# NodeBodyControl.net
KiCad netlist of a schematic drawn in Altium Designer
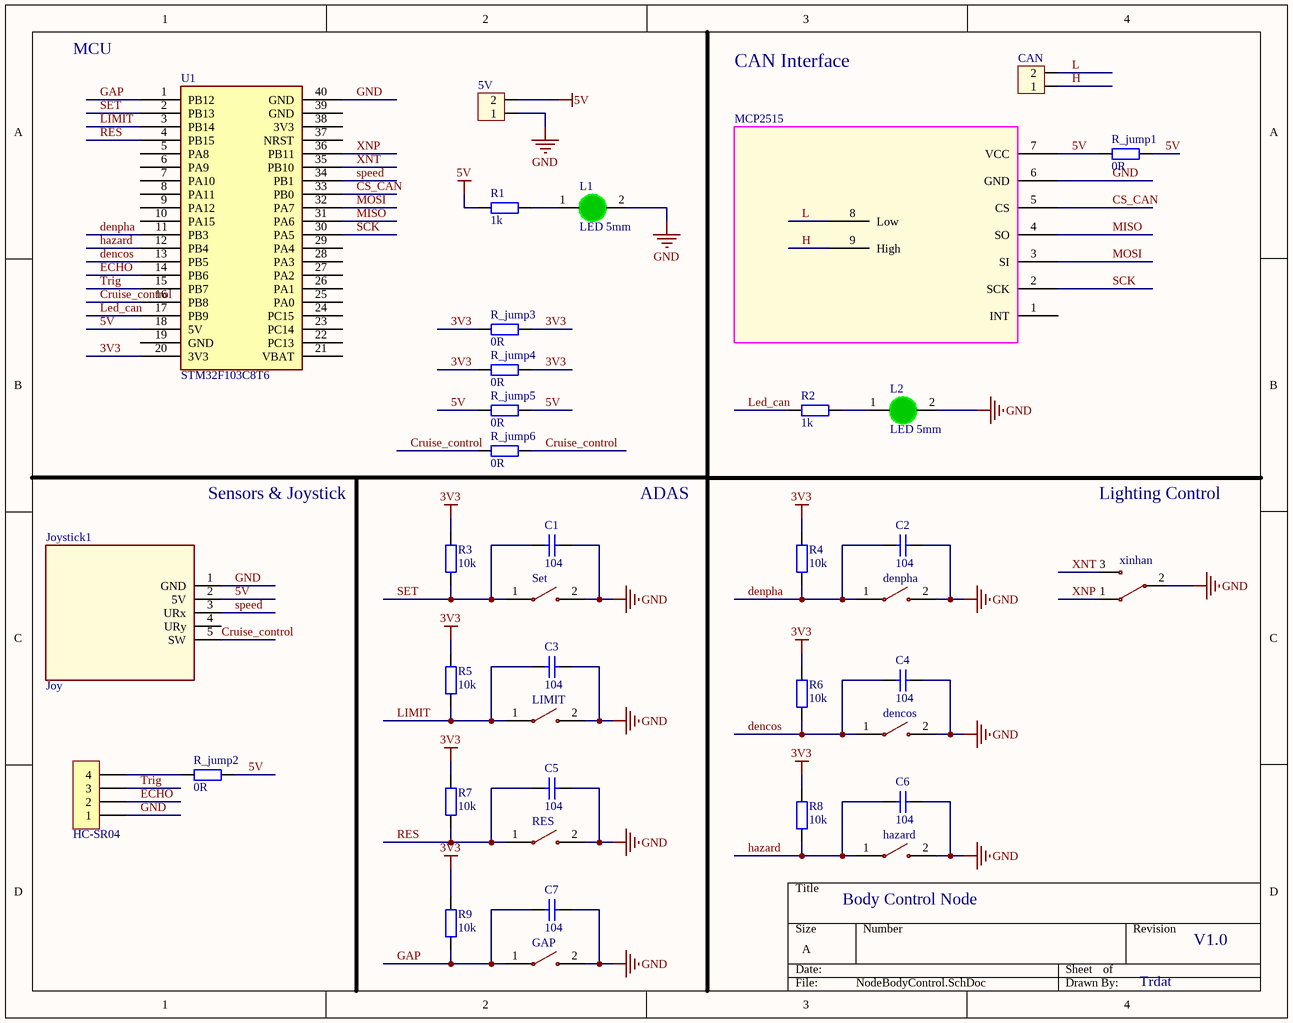
[diagram p0: NodeBodyControl.SchDoc]

(export (version "E")
  (design (tool "Eeschema 10.0.6"))
  (components
    (comp (ref "5V")
      (value "Header 2P 2.54 Duc Cong")
      (footprint "Header 2P DC 2.54")
      (description "Cắm")
      (libsource (lib "Altium_Lib_by_KhueNguyenCreator") (part "Header 2P 2.54 Duc Cong"))
    )
    (comp (ref "C1")
      (value "104")
      (footprint "tu gom")
      (description "Cắm")
      (libsource (lib "Altium_Lib_by_KhueNguyenCreator") (part "Tu gom 104 50V"))
    )
    (comp (ref "C2")
      (value "104")
      (footprint "tu gom")
      (description "Cắm")
      (libsource (lib "Altium_Lib_by_KhueNguyenCreator") (part "Tu gom 104 50V"))
    )
    (comp (ref "C3")
      (value "104")
      (footprint "tu gom")
      (description "Cắm")
      (libsource (lib "Altium_Lib_by_KhueNguyenCreator") (part "Tu gom 104 50V"))
    )
    (comp (ref "C4")
      (value "104")
      (footprint "tu gom")
      (description "Cắm")
      (libsource (lib "Altium_Lib_by_KhueNguyenCreator") (part "Tu gom 104 50V"))
    )
    (comp (ref "C5")
      (value "104")
      (footprint "tu gom")
      (description "Cắm")
      (libsource (lib "Altium_Lib_by_KhueNguyenCreator") (part "Tu gom 104 50V"))
    )
    (comp (ref "C6")
      (value "104")
      (footprint "tu gom")
      (description "Cắm")
      (libsource (lib "Altium_Lib_by_KhueNguyenCreator") (part "Tu gom 104 50V"))
    )
    (comp (ref "C7")
      (value "104")
      (footprint "tu gom")
      (description "Cắm")
      (libsource (lib "Altium_Lib_by_KhueNguyenCreator") (part "Tu gom 104 50V"))
    )
    (comp (ref "CAN")
      (value "~")
      (footprint "Header 2P DC 2.54")
      (description "Cắm")
      (libsource (lib "Altium_Lib_by_KhueNguyenCreator") (part "Header 2P 2.54 Duc Cong"))
    )
    (comp (ref "dencos")
      (value "PUSH_BUTTON_12X12")
      (footprint "PUSH_BUTTON_12X12_YELLOW")
      (description "Push Button Tactile Switch PTH 4 Pins 12x12mm.")
      (libsource (lib "Buttons & Switches") (part "PUSH_BUTTON_12X12"))
    )
    (comp (ref "denpha")
      (value "PUSH_BUTTON_12X12")
      (footprint "PUSH_BUTTON_12X12_YELLOW")
      (description "Push Button Tactile Switch PTH 4 Pins 12x12mm.")
      (libsource (lib "Buttons & Switches") (part "PUSH_BUTTON_12X12"))
    )
    (comp (ref "GAP")
      (value "PUSH_BUTTON_12X12")
      (footprint "PUSH_BUTTON_12X12_YELLOW")
      (description "Push Button Tactile Switch PTH 4 Pins 12x12mm.")
      (libsource (lib "Buttons & Switches") (part "PUSH_BUTTON_12X12"))
    )
    (comp (ref "H1")
      (value "HC-SR04")
      (footprint "Header 4P DC 2.54")
      (description "Cắm")
      (libsource (lib "My_Component_Library") (part "Header 4P 2.54 Duc Cong"))
    )
    (comp (ref "hazard")
      (value "PUSH_BUTTON_12X12")
      (footprint "PUSH_BUTTON_12X12_RED")
      (description "Push Button Tactile Switch PTH 4 Pins 12x12mm.")
      (libsource (lib "Buttons & Switches") (part "PUSH_BUTTON_12X12"))
    )
    (comp (ref "Joystick1")
      (value "Joy")
      (footprint "Joystick")
      (libsource (lib "My_Component_Library") (part "Joy"))
    )
    (comp (ref "L1")
      (value "LED 5mm")
      (footprint "LED-5MM-Green")
      (description "Cắm")
      (libsource (lib "Altium_Lib_by_KhueNguyenCreator") (part "LED 5mm Xanh La"))
    )
    (comp (ref "L2")
      (value "LED 5mm")
      (footprint "LED-5MM-Green")
      (description "Cắm")
      (libsource (lib "Altium_Lib_by_KhueNguyenCreator") (part "LED 5mm Xanh La"))
    )
    (comp (ref "LIMIT")
      (value "PUSH_BUTTON_12X12")
      (footprint "PUSH_BUTTON_12X12_YELLOW")
      (description "Push Button Tactile Switch PTH 4 Pins 12x12mm.")
      (libsource (lib "Buttons & Switches") (part "PUSH_BUTTON_12X12"))
    )
    (comp (ref "MCP2515")
      (value "MCP2515")
      (footprint "MCP2515_MODULE")
      (libsource (lib "My_Component_Library") (part "MCP2515"))
    )
    (comp (ref "R1")
      (value "1k")
      (footprint "tro vach 1/4w")
      (description "Cắm")
      (libsource (lib "Altium_Lib_by_KhueNguyenCreator") (part "Tro Vach 1/4W 5% 1k"))
    )
    (comp (ref "R2")
      (value "1k")
      (footprint "tro vach 1/4w")
      (description "Cắm")
      (libsource (lib "Altium_Lib_by_KhueNguyenCreator") (part "Tro Vach 1/4W 5% 1k"))
    )
    (comp (ref "R3")
      (value "10k")
      (footprint "tro vach 1/4w")
      (description "Căm")
      (libsource (lib "Altium_Lib_by_KhueNguyenCreator") (part "Tro Vach 1/4W 5% 10k"))
    )
    (comp (ref "R4")
      (value "10k")
      (footprint "tro vach 1/4w")
      (description "Căm")
      (libsource (lib "Altium_Lib_by_KhueNguyenCreator") (part "Tro Vach 1/4W 5% 10k"))
    )
    (comp (ref "R5")
      (value "10k")
      (footprint "tro vach 1/4w")
      (description "Căm")
      (libsource (lib "Altium_Lib_by_KhueNguyenCreator") (part "Tro Vach 1/4W 5% 10k"))
    )
    (comp (ref "R6")
      (value "10k")
      (footprint "tro vach 1/4w")
      (description "Căm")
      (libsource (lib "Altium_Lib_by_KhueNguyenCreator") (part "Tro Vach 1/4W 5% 10k"))
    )
    (comp (ref "R7")
      (value "10k")
      (footprint "tro vach 1/4w")
      (description "Căm")
      (libsource (lib "Altium_Lib_by_KhueNguyenCreator") (part "Tro Vach 1/4W 5% 10k"))
    )
    (comp (ref "R8")
      (value "10k")
      (footprint "tro vach 1/4w")
      (description "Căm")
      (libsource (lib "Altium_Lib_by_KhueNguyenCreator") (part "Tro Vach 1/4W 5% 10k"))
    )
    (comp (ref "R9")
      (value "10k")
      (footprint "tro vach 1/4w")
      (description "Căm")
      (libsource (lib "Altium_Lib_by_KhueNguyenCreator") (part "Tro Vach 1/4W 5% 10k"))
    )
    (comp (ref "RES")
      (value "PUSH_BUTTON_12X12")
      (footprint "PUSH_BUTTON_12X12_YELLOW")
      (description "Push Button Tactile Switch PTH 4 Pins 12x12mm.")
      (libsource (lib "Buttons & Switches") (part "PUSH_BUTTON_12X12"))
    )
    (comp (ref "R_jump1")
      (value "0R")
      (footprint "tro vach 1/4w")
      (description "Cắm")
      (libsource (lib "Altium_Lib_by_KhueNguyenCreator") (part "Tro Vach 1/4W 5% 0.11R"))
    )
    (comp (ref "R_jump2")
      (value "0R")
      (footprint "tro vach 1/4w")
      (description "Cắm")
      (libsource (lib "Altium_Lib_by_KhueNguyenCreator") (part "Tro Vach 1/4W 5% 0.11R"))
    )
    (comp (ref "R_jump3")
      (value "0R")
      (footprint "tro vach 1/4w")
      (description "Cắm")
      (libsource (lib "Altium_Lib_by_KhueNguyenCreator") (part "Tro Vach 1/4W 5% 0.11R"))
    )
    (comp (ref "R_jump4")
      (value "0R")
      (footprint "tro vach 1/4w")
      (description "Cắm")
      (libsource (lib "Altium_Lib_by_KhueNguyenCreator") (part "Tro Vach 1/4W 5% 0.11R"))
    )
    (comp (ref "R_jump5")
      (value "0R")
      (footprint "tro vach 1/4w")
      (description "Cắm")
      (libsource (lib "Altium_Lib_by_KhueNguyenCreator") (part "Tro Vach 1/4W 5% 0.11R"))
    )
    (comp (ref "R_jump6")
      (value "0R")
      (footprint "tro vach 1/4w")
      (description "Cắm")
      (libsource (lib "Altium_Lib_by_KhueNguyenCreator") (part "Tro Vach 1/4W 5% 0.11R"))
    )
    (comp (ref "Set")
      (value "PUSH_BUTTON_12X12")
      (footprint "PUSH_BUTTON_12X12_YELLOW")
      (description "Push Button Tactile Switch PTH 4 Pins 12x12mm.")
      (libsource (lib "Buttons & Switches") (part "PUSH_BUTTON_12X12"))
    )
    (comp (ref "U1")
      (value "STM32F103C8T6")
      (footprint "Stm32 BluePill")
      (description "Designed By @Alixahedi")
      (libsource (lib "Stm32 Blue Pill") (part "BluePill"))
    )
    (comp (ref "xinhan")
      (value "~")
      (footprint "TOGGLE_SWITCH_SPDT")
      (description "Toggle Switch SPDT, 125V AC, 6A, 33x13x7mm.")
      (libsource (lib "Buttons & Switches") (part "TOGGLE_SWITCH_SPDT"))
    )
  )
  (nets
    (net (code "1") (name "/CS_CAN") (class "Default")
      (node (ref "MCP2515") (pin "5") (pinfunction "CS_5") (pintype "passive"))
      (node (ref "U1") (pin "33") (pinfunction "PB0_33") (pintype "passive"))
    )
    (net (code "2") (name "/Cruise_control") (class "Default")
      (node (ref "Joystick1") (pin "5") (pinfunction "SW_5") (pintype "passive"))
      (node (ref "R_jump6") (pin "1") (pinfunction "1_1") (pintype "passive"))
      (node (ref "R_jump6") (pin "2") (pinfunction "2_2") (pintype "passive"))
      (node (ref "U1") (pin "16") (pinfunction "PB8_16") (pintype "passive"))
    )
    (net (code "3") (name "/ECHO") (class "Default")
      (node (ref "H1") (pin "2") (pinfunction "2_2") (pintype "passive"))
      (node (ref "U1") (pin "14") (pinfunction "PB6_14") (pintype "passive"))
    )
    (net (code "4") (name "/GAP") (class "Default")
      (node (ref "C7") (pin "2") (pinfunction "2_2") (pintype "passive"))
      (node (ref "GAP") (pin "1") (pinfunction "1_1") (pintype "passive"))
      (node (ref "R9") (pin "1") (pinfunction "1_1") (pintype "passive"))
      (node (ref "U1") (pin "1") (pinfunction "PB12_1") (pintype "passive"))
    )
    (net (code "5") (name "/H") (class "Default")
      (node (ref "CAN") (pin "1") (pinfunction "1_1") (pintype "passive"))
      (node (ref "MCP2515") (pin "9") (pinfunction "High_9") (pintype "passive"))
    )
    (net (code "6") (name "/L") (class "Default")
      (node (ref "CAN") (pin "2") (pinfunction "2_2") (pintype "passive"))
      (node (ref "MCP2515") (pin "8") (pinfunction "Low_8") (pintype "passive"))
    )
    (net (code "7") (name "/LIMIT") (class "Default")
      (node (ref "C3") (pin "2") (pinfunction "2_2") (pintype "passive"))
      (node (ref "LIMIT") (pin "1") (pinfunction "1_1") (pintype "passive"))
      (node (ref "R5") (pin "1") (pinfunction "1_1") (pintype "passive"))
      (node (ref "U1") (pin "3") (pinfunction "PB14_3") (pintype "passive"))
    )
    (net (code "8") (name "/Led_can") (class "Default")
      (node (ref "R2") (pin "1") (pinfunction "1_1") (pintype "passive"))
      (node (ref "U1") (pin "17") (pinfunction "PB9_17") (pintype "passive"))
    )
    (net (code "9") (name "/MISO") (class "Default")
      (node (ref "MCP2515") (pin "4") (pinfunction "SO_4") (pintype "passive"))
      (node (ref "U1") (pin "31") (pinfunction "PA6_31") (pintype "passive"))
    )
    (net (code "10") (name "/MOSI") (class "Default")
      (node (ref "MCP2515") (pin "3") (pinfunction "SI_3") (pintype "passive"))
      (node (ref "U1") (pin "32") (pinfunction "PA7_32") (pintype "passive"))
    )
    (net (code "11") (name "/RES") (class "Default")
      (node (ref "C5") (pin "2") (pinfunction "2_2") (pintype "passive"))
      (node (ref "R7") (pin "1") (pinfunction "1_1") (pintype "passive"))
      (node (ref "RES") (pin "1") (pinfunction "1_1") (pintype "passive"))
      (node (ref "U1") (pin "4") (pinfunction "PB15_4") (pintype "passive"))
    )
    (net (code "12") (name "/SCK") (class "Default")
      (node (ref "MCP2515") (pin "2") (pinfunction "SCK_2") (pintype "passive"))
      (node (ref "U1") (pin "30") (pinfunction "PA5_30") (pintype "passive"))
    )
    (net (code "13") (name "/SET") (class "Default")
      (node (ref "C1") (pin "2") (pinfunction "2_2") (pintype "passive"))
      (node (ref "R3") (pin "1") (pinfunction "1_1") (pintype "passive"))
      (node (ref "Set") (pin "1") (pinfunction "1_1") (pintype "passive"))
      (node (ref "U1") (pin "2") (pinfunction "PB13_2") (pintype "passive"))
    )
    (net (code "14") (name "/Trig") (class "Default")
      (node (ref "H1") (pin "3") (pinfunction "3_3") (pintype "passive"))
      (node (ref "U1") (pin "15") (pinfunction "PB7_15") (pintype "passive"))
    )
    (net (code "15") (name "/XNP") (class "Default")
      (node (ref "U1") (pin "36") (pinfunction "PB11_36") (pintype "passive"))
      (node (ref "xinhan") (pin "1") (pinfunction "1_1") (pintype "passive"))
    )
    (net (code "16") (name "/XNT") (class "Default")
      (node (ref "U1") (pin "35") (pinfunction "PB10_35") (pintype "passive"))
      (node (ref "xinhan") (pin "3") (pinfunction "3_3") (pintype "passive"))
    )
    (net (code "17") (name "/dencos") (class "Default")
      (node (ref "C4") (pin "2") (pinfunction "2_2") (pintype "passive"))
      (node (ref "R6") (pin "1") (pinfunction "1_1") (pintype "passive"))
      (node (ref "U1") (pin "13") (pinfunction "PB5_13") (pintype "passive"))
      (node (ref "dencos") (pin "1") (pinfunction "1_1") (pintype "passive"))
    )
    (net (code "18") (name "/denpha") (class "Default")
      (node (ref "C2") (pin "2") (pinfunction "2_2") (pintype "passive"))
      (node (ref "R4") (pin "1") (pinfunction "1_1") (pintype "passive"))
      (node (ref "U1") (pin "11") (pinfunction "PB3_11") (pintype "passive"))
      (node (ref "denpha") (pin "1") (pinfunction "1_1") (pintype "passive"))
    )
    (net (code "19") (name "/hazard") (class "Default")
      (node (ref "C6") (pin "2") (pinfunction "2_2") (pintype "passive"))
      (node (ref "R8") (pin "1") (pinfunction "1_1") (pintype "passive"))
      (node (ref "U1") (pin "12") (pinfunction "PB4_12") (pintype "passive"))
      (node (ref "hazard") (pin "1") (pinfunction "1_1") (pintype "passive"))
    )
    (net (code "20") (name "/speed") (class "Default")
      (node (ref "Joystick1") (pin "3") (pinfunction "URx_3") (pintype "passive"))
      (node (ref "U1") (pin "34") (pinfunction "PB1_34") (pintype "passive"))
    )
    (net (code "21") (name "3V3") (class "Default")
      (node (ref "R3") (pin "2") (pinfunction "2_2") (pintype "passive"))
      (node (ref "R4") (pin "2") (pinfunction "2_2") (pintype "passive"))
      (node (ref "R5") (pin "2") (pinfunction "2_2") (pintype "passive"))
      (node (ref "R6") (pin "2") (pinfunction "2_2") (pintype "passive"))
      (node (ref "R7") (pin "2") (pinfunction "2_2") (pintype "passive"))
      (node (ref "R8") (pin "2") (pinfunction "2_2") (pintype "passive"))
      (node (ref "R9") (pin "2") (pinfunction "2_2") (pintype "passive"))
      (node (ref "R_jump3") (pin "1") (pinfunction "1_1") (pintype "passive"))
      (node (ref "R_jump3") (pin "2") (pinfunction "2_2") (pintype "passive"))
      (node (ref "R_jump4") (pin "1") (pinfunction "1_1") (pintype "passive"))
      (node (ref "R_jump4") (pin "2") (pinfunction "2_2") (pintype "passive"))
      (node (ref "U1") (pin "20") (pinfunction "3V3_20") (pintype "passive"))
    )
    (net (code "22") (name "5V") (class "Default")
      (node (ref "5V") (pin "2") (pinfunction "2_2") (pintype "passive"))
      (node (ref "Joystick1") (pin "2") (pinfunction "5V_2") (pintype "power_in"))
      (node (ref "MCP2515") (pin "7") (pinfunction "VCC_7") (pintype "power_in"))
      (node (ref "R1") (pin "1") (pinfunction "1_1") (pintype "passive"))
      (node (ref "R_jump1") (pin "1") (pinfunction "1_1") (pintype "passive"))
      (node (ref "R_jump1") (pin "2") (pinfunction "2_2") (pintype "passive"))
      (node (ref "R_jump2") (pin "2") (pinfunction "2_2") (pintype "passive"))
      (node (ref "R_jump5") (pin "1") (pinfunction "1_1") (pintype "passive"))
      (node (ref "R_jump5") (pin "2") (pinfunction "2_2") (pintype "passive"))
      (node (ref "U1") (pin "18") (pinfunction "5V_18") (pintype "passive"))
    )
    (net (code "23") (name "GND") (class "Default")
      (node (ref "5V") (pin "1") (pinfunction "1_1") (pintype "passive"))
      (node (ref "C1") (pin "1") (pinfunction "1_1") (pintype "passive"))
      (node (ref "C2") (pin "1") (pinfunction "1_1") (pintype "passive"))
      (node (ref "C3") (pin "1") (pinfunction "1_1") (pintype "passive"))
      (node (ref "C4") (pin "1") (pinfunction "1_1") (pintype "passive"))
      (node (ref "C5") (pin "1") (pinfunction "1_1") (pintype "passive"))
      (node (ref "C6") (pin "1") (pinfunction "1_1") (pintype "passive"))
      (node (ref "C7") (pin "1") (pinfunction "1_1") (pintype "passive"))
      (node (ref "GAP") (pin "2") (pinfunction "2_2") (pintype "passive"))
      (node (ref "H1") (pin "1") (pinfunction "1_1") (pintype "passive"))
      (node (ref "Joystick1") (pin "1") (pinfunction "GND_1") (pintype "power_in"))
      (node (ref "L1") (pin "2") (pinfunction "K_2") (pintype "passive"))
      (node (ref "L2") (pin "2") (pinfunction "K_2") (pintype "passive"))
      (node (ref "LIMIT") (pin "2") (pinfunction "2_2") (pintype "passive"))
      (node (ref "MCP2515") (pin "6") (pinfunction "GND_6") (pintype "power_in"))
      (node (ref "RES") (pin "2") (pinfunction "2_2") (pintype "passive"))
      (node (ref "Set") (pin "2") (pinfunction "2_2") (pintype "passive"))
      (node (ref "U1") (pin "40") (pinfunction "GND_40") (pintype "passive"))
      (node (ref "dencos") (pin "2") (pinfunction "2_2") (pintype "passive"))
      (node (ref "denpha") (pin "2") (pinfunction "2_2") (pintype "passive"))
      (node (ref "hazard") (pin "2") (pinfunction "2_2") (pintype "passive"))
      (node (ref "xinhan") (pin "2") (pinfunction "2_2") (pintype "passive"))
    )
    (net (code "24") (name "Net-(H1-Pad4)") (class "Default")
      (node (ref "H1") (pin "4") (pinfunction "4_4") (pintype "passive"))
      (node (ref "R_jump2") (pin "1") (pinfunction "1_1") (pintype "passive"))
    )
    (net (code "25") (name "Net-(L1-A)") (class "Default")
      (node (ref "L1") (pin "1") (pinfunction "A_1") (pintype "passive"))
      (node (ref "R1") (pin "2") (pinfunction "2_2") (pintype "passive"))
    )
    (net (code "26") (name "Net-(L2-A)") (class "Default")
      (node (ref "L2") (pin "1") (pinfunction "A_1") (pintype "passive"))
      (node (ref "R2") (pin "2") (pinfunction "2_2") (pintype "passive"))
    )
    (net (code "27") (name "unconnected-(Joystick1-URy-Pad4)") (class "Default")
      (node (ref "Joystick1") (pin "4") (pinfunction "URy_4") (pintype "passive"))
    )
    (net (code "28") (name "unconnected-(MCP2515-INT-Pad1)") (class "Default")
      (node (ref "MCP2515") (pin "1") (pinfunction "INT_1") (pintype "passive"))
    )
    (net (code "29") (name "unconnected-(U1-3V3-Pad38)") (class "Default")
      (node (ref "U1") (pin "38") (pinfunction "3V3_38") (pintype "passive"))
    )
    (net (code "30") (name "unconnected-(U1-GND-Pad19)") (class "Default")
      (node (ref "U1") (pin "19") (pinfunction "GND_19") (pintype "passive"))
    )
    (net (code "31") (name "unconnected-(U1-GND-Pad39)") (class "Default")
      (node (ref "U1") (pin "39") (pinfunction "GND_39") (pintype "passive"))
    )
    (net (code "32") (name "unconnected-(U1-NRST-Pad37)") (class "Default")
      (node (ref "U1") (pin "37") (pinfunction "NRST_37") (pintype "passive"))
    )
    (net (code "33") (name "unconnected-(U1-PA0-Pad25)") (class "Default")
      (node (ref "U1") (pin "25") (pinfunction "PA0_25") (pintype "passive"))
    )
    (net (code "34") (name "unconnected-(U1-PA1-Pad26)") (class "Default")
      (node (ref "U1") (pin "26") (pinfunction "PA1_26") (pintype "passive"))
    )
    (net (code "35") (name "unconnected-(U1-PA2-Pad27)") (class "Default")
      (node (ref "U1") (pin "27") (pinfunction "PA2_27") (pintype "passive"))
    )
    (net (code "36") (name "unconnected-(U1-PA3-Pad28)") (class "Default")
      (node (ref "U1") (pin "28") (pinfunction "PA3_28") (pintype "passive"))
    )
    (net (code "37") (name "unconnected-(U1-PA4-Pad29)") (class "Default")
      (node (ref "U1") (pin "29") (pinfunction "PA4_29") (pintype "passive"))
    )
    (net (code "38") (name "unconnected-(U1-PA8-Pad5)") (class "Default")
      (node (ref "U1") (pin "5") (pinfunction "PA8_5") (pintype "passive"))
    )
    (net (code "39") (name "unconnected-(U1-PA9-Pad6)") (class "Default")
      (node (ref "U1") (pin "6") (pinfunction "PA9_6") (pintype "passive"))
    )
    (net (code "40") (name "unconnected-(U1-PA10-Pad7)") (class "Default")
      (node (ref "U1") (pin "7") (pinfunction "PA10_7") (pintype "passive"))
    )
    (net (code "41") (name "unconnected-(U1-PA11-Pad8)") (class "Default")
      (node (ref "U1") (pin "8") (pinfunction "PA11_8") (pintype "passive"))
    )
    (net (code "42") (name "unconnected-(U1-PA12-Pad9)") (class "Default")
      (node (ref "U1") (pin "9") (pinfunction "PA12_9") (pintype "passive"))
    )
    (net (code "43") (name "unconnected-(U1-PA15-Pad10)") (class "Default")
      (node (ref "U1") (pin "10") (pinfunction "PA15_10") (pintype "passive"))
    )
    (net (code "44") (name "unconnected-(U1-PC13-Pad22)") (class "Default")
      (node (ref "U1") (pin "22") (pinfunction "PC13_22") (pintype "passive"))
    )
    (net (code "45") (name "unconnected-(U1-PC14-Pad23)") (class "Default")
      (node (ref "U1") (pin "23") (pinfunction "PC14_23") (pintype "passive"))
    )
    (net (code "46") (name "unconnected-(U1-PC15-Pad24)") (class "Default")
      (node (ref "U1") (pin "24") (pinfunction "PC15_24") (pintype "passive"))
    )
    (net (code "47") (name "unconnected-(U1-VBAT-Pad21)") (class "Default")
      (node (ref "U1") (pin "21") (pinfunction "VBAT_21") (pintype "passive"))
    )
  )
)
